# Brain.net
KiCad netlist of a schematic drawn in EAGLE
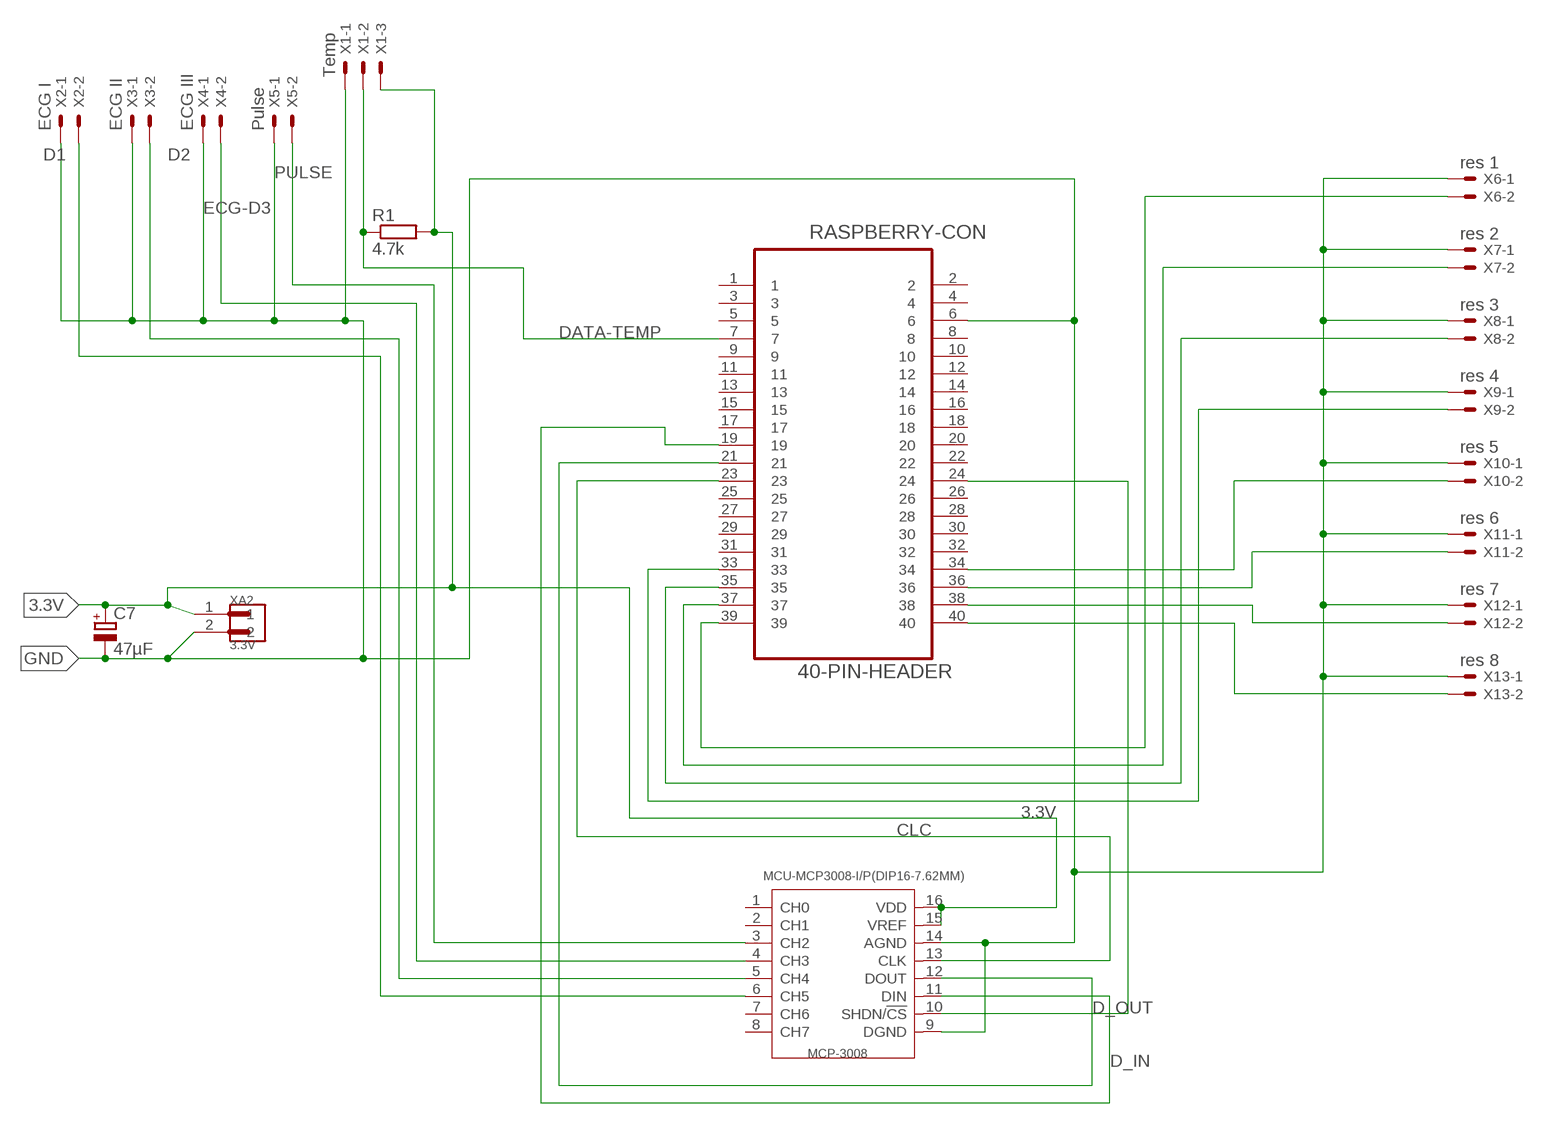
[diagram p0: schematic, sheet 1]

(export (version "E")
  (design (tool "Eeschema 10.0.6"))
  (components
    (comp (ref "C7")
      (value "47µF")
      (footprint "eagle-import:E2,5-6E")
      (libsource (lib "eagle-import") (part "CPOL-EUE2,5-6E"))
    )
    (comp (ref "MCP-3008")
      (value "MCU-MCP3008-I/P(DIP16-7.62MM)")
      (footprint "eagle-import:DIP16-2.54-19.2X7.62MM")
      (fields (field (name "MF") "Microchip") (field (name "MP") "MCP3008-I/P"))
      (libsource (lib "eagle-import") (part "MCU-MCP3008-I/P(DIP16-7.62MM)"))
    )
    (comp (ref "R1")
      (value "4.7k")
      (footprint "eagle-import:0207_7")
      (libsource (lib "eagle-import") (part "R-EU_0207/7"))
    )
    (comp (ref "RASPBERRY-CON")
      (value "40-PIN-HEADER")
      (footprint "eagle-import:SAMTEC_TSW-120-09-F-Q")
      (fields (field (name "MF") "Samtec") (field (name "MP") "TSW-120-09-F-Q"))
      (libsource (lib "eagle-import") (part "TSW-120-09-F-Q"))
    )
    (comp (ref "X1")
      (value "Temp")
      (footprint "eagle-import:JST-XH-03-PACKAGE-LONG-PAD")
      (libsource (lib "eagle-import") (part "JST-XH-03-PIN-LONG-PAD"))
    )
    (comp (ref "X2")
      (value "ECG I")
      (footprint "eagle-import:JST-XH-02-PACKAGE-LONG-PAD")
      (libsource (lib "eagle-import") (part "JST-XH-02-PIN-LONG-PAD"))
    )
    (comp (ref "X3")
      (value "ECG II")
      (footprint "eagle-import:JST-XH-02-PACKAGE-LONG-PAD")
      (libsource (lib "eagle-import") (part "JST-XH-02-PIN-LONG-PAD"))
    )
    (comp (ref "X4")
      (value "ECG III")
      (footprint "eagle-import:JST-XH-02-PACKAGE-LONG-PAD")
      (libsource (lib "eagle-import") (part "JST-XH-02-PIN-LONG-PAD"))
    )
    (comp (ref "X5")
      (value "Pulse")
      (footprint "eagle-import:JST-XH-02-PACKAGE-LONG-PAD")
      (libsource (lib "eagle-import") (part "JST-XH-02-PIN-LONG-PAD"))
    )
    (comp (ref "X6")
      (value "res 1")
      (footprint "eagle-import:JST-XH-02-PACKAGE-LONG-PAD")
      (libsource (lib "eagle-import") (part "JST-XH-02-PIN-LONG-PAD"))
    )
    (comp (ref "X7")
      (value "res 2")
      (footprint "eagle-import:JST-XH-02-PACKAGE-LONG-PAD")
      (libsource (lib "eagle-import") (part "JST-XH-02-PIN-LONG-PAD"))
    )
    (comp (ref "X8")
      (value "res 3")
      (footprint "eagle-import:JST-XH-02-PACKAGE-LONG-PAD")
      (libsource (lib "eagle-import") (part "JST-XH-02-PIN-LONG-PAD"))
    )
    (comp (ref "X9")
      (value "res 4")
      (footprint "eagle-import:JST-XH-02-PACKAGE-LONG-PAD")
      (libsource (lib "eagle-import") (part "JST-XH-02-PIN-LONG-PAD"))
    )
    (comp (ref "X10")
      (value "res 5")
      (footprint "eagle-import:JST-XH-02-PACKAGE-LONG-PAD")
      (libsource (lib "eagle-import") (part "JST-XH-02-PIN-LONG-PAD"))
    )
    (comp (ref "X11")
      (value "res 6")
      (footprint "eagle-import:JST-XH-02-PACKAGE-LONG-PAD")
      (libsource (lib "eagle-import") (part "JST-XH-02-PIN-LONG-PAD"))
    )
    (comp (ref "X12")
      (value "res 7")
      (footprint "eagle-import:JST-XH-02-PACKAGE-LONG-PAD")
      (libsource (lib "eagle-import") (part "JST-XH-02-PIN-LONG-PAD"))
    )
    (comp (ref "X13")
      (value "res 8")
      (footprint "eagle-import:JST-XH-02-PACKAGE-LONG-PAD")
      (libsource (lib "eagle-import") (part "JST-XH-02-PIN-LONG-PAD"))
    )
    (comp (ref "XA2")
      (value "3.3V")
      (footprint "eagle-import:JST_B2P-VH(LF)(SN)")
      (fields (field (name "MF") "JST") (field (name "MP") "B2P-VH_LF__SN_"))
      (libsource (lib "eagle-import") (part "B2P-VH(LF)(SN)"))
    )
  )
  (nets
    (net (code "1") (name "/CLC") (class "Default")
      (node (ref "MCP-3008") (pin "13") (pinfunction "CLK_13") (pintype "output"))
      (node (ref "RASPBERRY-CON") (pin "23") (pinfunction "23_23") (pintype "passive"))
    )
    (net (code "2") (name "/D1") (class "Default")
      (node (ref "MCP-3008") (pin "6") (pinfunction "CH5_6") (pintype "input"))
      (node (ref "X2") (pin "2") (pinfunction "S_2") (pintype "passive"))
    )
    (net (code "3") (name "/D2") (class "Default")
      (node (ref "MCP-3008") (pin "5") (pinfunction "CH4_5") (pintype "input"))
      (node (ref "X3") (pin "2") (pinfunction "S_2") (pintype "passive"))
    )
    (net (code "4") (name "/DATA-TEMP") (class "Default")
      (node (ref "R1") (pin "1") (pinfunction "1_1") (pintype "passive"))
      (node (ref "RASPBERRY-CON") (pin "7") (pinfunction "7_7") (pintype "passive"))
      (node (ref "X1") (pin "2") (pinfunction "S_2") (pintype "passive"))
    )
    (net (code "5") (name "/D_IN") (class "Default")
      (node (ref "MCP-3008") (pin "11") (pinfunction "DIN_11") (pintype "input"))
      (node (ref "RASPBERRY-CON") (pin "19") (pinfunction "19_19") (pintype "passive"))
    )
    (net (code "6") (name "/D_OUT") (class "Default")
      (node (ref "MCP-3008") (pin "12") (pinfunction "DOUT_12") (pintype "input"))
      (node (ref "RASPBERRY-CON") (pin "21") (pinfunction "21_21") (pintype "passive"))
    )
    (net (code "7") (name "/ECG-D3") (class "Default")
      (node (ref "MCP-3008") (pin "4") (pinfunction "CH3_4") (pintype "input"))
      (node (ref "X4") (pin "2") (pinfunction "S_2") (pintype "passive"))
    )
    (net (code "8") (name "/PULSE") (class "Default")
      (node (ref "MCP-3008") (pin "3") (pinfunction "CH2_3") (pintype "output"))
      (node (ref "X5") (pin "2") (pinfunction "S_2") (pintype "passive"))
    )
    (net (code "9") (name "3.3V") (class "Default")
      (node (ref "C7") (pin "+") (pinfunction "+_+") (pintype "passive"))
      (node (ref "MCP-3008") (pin "15") (pinfunction "VREF_15") (pintype "input"))
      (node (ref "MCP-3008") (pin "16") (pinfunction "VDD_16") (pintype "power_in"))
      (node (ref "R1") (pin "2") (pinfunction "2_2") (pintype "passive"))
      (node (ref "X1") (pin "3") (pinfunction "S_3") (pintype "passive"))
      (node (ref "XA2") (pin "1") (pinfunction "1_1") (pintype "passive"))
    )
    (net (code "10") (name "GND") (class "Default")
      (node (ref "C7") (pin "-") (pinfunction "-_-") (pintype "passive"))
      (node (ref "MCP-3008") (pin "14") (pinfunction "AGND_14") (pintype "input"))
      (node (ref "MCP-3008") (pin "9") (pinfunction "DGND_9") (pintype "output"))
      (node (ref "RASPBERRY-CON") (pin "6") (pinfunction "6_6") (pintype "passive"))
      (node (ref "X1") (pin "1") (pinfunction "S_1") (pintype "passive"))
      (node (ref "X10") (pin "1") (pinfunction "S_1") (pintype "passive"))
      (node (ref "X11") (pin "1") (pinfunction "S_1") (pintype "passive"))
      (node (ref "X12") (pin "1") (pinfunction "S_1") (pintype "passive"))
      (node (ref "X13") (pin "1") (pinfunction "S_1") (pintype "passive"))
      (node (ref "X2") (pin "1") (pinfunction "S_1") (pintype "passive"))
      (node (ref "X3") (pin "1") (pinfunction "S_1") (pintype "passive"))
      (node (ref "X4") (pin "1") (pinfunction "S_1") (pintype "passive"))
      (node (ref "X5") (pin "1") (pinfunction "S_1") (pintype "passive"))
      (node (ref "X6") (pin "1") (pinfunction "S_1") (pintype "passive"))
      (node (ref "X7") (pin "1") (pinfunction "S_1") (pintype "passive"))
      (node (ref "X8") (pin "1") (pinfunction "S_1") (pintype "passive"))
      (node (ref "X9") (pin "1") (pinfunction "S_1") (pintype "passive"))
      (node (ref "XA2") (pin "2") (pinfunction "2_2") (pintype "passive"))
    )
    (net (code "11") (name "Net-(MCP-3008-SHDN{slash}~{CS})") (class "Default")
      (node (ref "MCP-3008") (pin "10") (pinfunction "SHDN/~{CS}_10") (pintype "output"))
      (node (ref "RASPBERRY-CON") (pin "24") (pinfunction "24_24") (pintype "passive"))
    )
    (net (code "12") (name "Net-(X6B-S)") (class "Default")
      (node (ref "RASPBERRY-CON") (pin "39") (pinfunction "39_39") (pintype "passive"))
      (node (ref "X6") (pin "2") (pinfunction "S_2") (pintype "passive"))
    )
    (net (code "13") (name "Net-(X7B-S)") (class "Default")
      (node (ref "RASPBERRY-CON") (pin "37") (pinfunction "37_37") (pintype "passive"))
      (node (ref "X7") (pin "2") (pinfunction "S_2") (pintype "passive"))
    )
    (net (code "14") (name "Net-(X8B-S)") (class "Default")
      (node (ref "RASPBERRY-CON") (pin "35") (pinfunction "35_35") (pintype "passive"))
      (node (ref "X8") (pin "2") (pinfunction "S_2") (pintype "passive"))
    )
    (net (code "15") (name "Net-(X9B-S)") (class "Default")
      (node (ref "RASPBERRY-CON") (pin "33") (pinfunction "33_33") (pintype "passive"))
      (node (ref "X9") (pin "2") (pinfunction "S_2") (pintype "passive"))
    )
    (net (code "16") (name "Net-(X10B-S)") (class "Default")
      (node (ref "RASPBERRY-CON") (pin "34") (pinfunction "34_34") (pintype "passive"))
      (node (ref "X10") (pin "2") (pinfunction "S_2") (pintype "passive"))
    )
    (net (code "17") (name "Net-(X11B-S)") (class "Default")
      (node (ref "RASPBERRY-CON") (pin "36") (pinfunction "36_36") (pintype "passive"))
      (node (ref "X11") (pin "2") (pinfunction "S_2") (pintype "passive"))
    )
    (net (code "18") (name "Net-(X12B-S)") (class "Default")
      (node (ref "RASPBERRY-CON") (pin "38") (pinfunction "38_38") (pintype "passive"))
      (node (ref "X12") (pin "2") (pinfunction "S_2") (pintype "passive"))
    )
    (net (code "19") (name "Net-(X13B-S)") (class "Default")
      (node (ref "RASPBERRY-CON") (pin "40") (pinfunction "40_40") (pintype "passive"))
      (node (ref "X13") (pin "2") (pinfunction "S_2") (pintype "passive"))
    )
    (net (code "20") (name "unconnected-(MCP-3008-CH0-Pad1)") (class "Default")
      (node (ref "MCP-3008") (pin "1") (pinfunction "CH0_1") (pintype "output"))
    )
    (net (code "21") (name "unconnected-(MCP-3008-CH1-Pad2)") (class "Default")
      (node (ref "MCP-3008") (pin "2") (pinfunction "CH1_2") (pintype "input"))
    )
    (net (code "22") (name "unconnected-(MCP-3008-CH6-Pad7)") (class "Default")
      (node (ref "MCP-3008") (pin "7") (pinfunction "CH6_7") (pintype "output"))
    )
    (net (code "23") (name "unconnected-(MCP-3008-CH7-Pad8)") (class "Default")
      (node (ref "MCP-3008") (pin "8") (pinfunction "CH7_8") (pintype "input"))
    )
    (net (code "24") (name "unconnected-(RASPBERRY-CON-Pad1)") (class "Default")
      (node (ref "RASPBERRY-CON") (pin "1") (pinfunction "1_1") (pintype "passive"))
    )
    (net (code "25") (name "unconnected-(RASPBERRY-CON-Pad2)") (class "Default")
      (node (ref "RASPBERRY-CON") (pin "2") (pinfunction "2_2") (pintype "passive"))
    )
    (net (code "26") (name "unconnected-(RASPBERRY-CON-Pad3)") (class "Default")
      (node (ref "RASPBERRY-CON") (pin "3") (pinfunction "3_3") (pintype "passive"))
    )
    (net (code "27") (name "unconnected-(RASPBERRY-CON-Pad4)") (class "Default")
      (node (ref "RASPBERRY-CON") (pin "4") (pinfunction "4_4") (pintype "passive"))
    )
    (net (code "28") (name "unconnected-(RASPBERRY-CON-Pad5)") (class "Default")
      (node (ref "RASPBERRY-CON") (pin "5") (pinfunction "5_5") (pintype "passive"))
    )
    (net (code "29") (name "unconnected-(RASPBERRY-CON-Pad8)") (class "Default")
      (node (ref "RASPBERRY-CON") (pin "8") (pinfunction "8_8") (pintype "passive"))
    )
    (net (code "30") (name "unconnected-(RASPBERRY-CON-Pad9)") (class "Default")
      (node (ref "RASPBERRY-CON") (pin "9") (pinfunction "9_9") (pintype "passive"))
    )
    (net (code "31") (name "unconnected-(RASPBERRY-CON-Pad10)") (class "Default")
      (node (ref "RASPBERRY-CON") (pin "10") (pinfunction "10_10") (pintype "passive"))
    )
    (net (code "32") (name "unconnected-(RASPBERRY-CON-Pad11)") (class "Default")
      (node (ref "RASPBERRY-CON") (pin "11") (pinfunction "11_11") (pintype "passive"))
    )
    (net (code "33") (name "unconnected-(RASPBERRY-CON-Pad12)") (class "Default")
      (node (ref "RASPBERRY-CON") (pin "12") (pinfunction "12_12") (pintype "passive"))
    )
    (net (code "34") (name "unconnected-(RASPBERRY-CON-Pad13)") (class "Default")
      (node (ref "RASPBERRY-CON") (pin "13") (pinfunction "13_13") (pintype "passive"))
    )
    (net (code "35") (name "unconnected-(RASPBERRY-CON-Pad14)") (class "Default")
      (node (ref "RASPBERRY-CON") (pin "14") (pinfunction "14_14") (pintype "passive"))
    )
    (net (code "36") (name "unconnected-(RASPBERRY-CON-Pad15)") (class "Default")
      (node (ref "RASPBERRY-CON") (pin "15") (pinfunction "15_15") (pintype "passive"))
    )
    (net (code "37") (name "unconnected-(RASPBERRY-CON-Pad16)") (class "Default")
      (node (ref "RASPBERRY-CON") (pin "16") (pinfunction "16_16") (pintype "passive"))
    )
    (net (code "38") (name "unconnected-(RASPBERRY-CON-Pad17)") (class "Default")
      (node (ref "RASPBERRY-CON") (pin "17") (pinfunction "17_17") (pintype "passive"))
    )
    (net (code "39") (name "unconnected-(RASPBERRY-CON-Pad18)") (class "Default")
      (node (ref "RASPBERRY-CON") (pin "18") (pinfunction "18_18") (pintype "passive"))
    )
    (net (code "40") (name "unconnected-(RASPBERRY-CON-Pad20)") (class "Default")
      (node (ref "RASPBERRY-CON") (pin "20") (pinfunction "20_20") (pintype "passive"))
    )
    (net (code "41") (name "unconnected-(RASPBERRY-CON-Pad22)") (class "Default")
      (node (ref "RASPBERRY-CON") (pin "22") (pinfunction "22_22") (pintype "passive"))
    )
    (net (code "42") (name "unconnected-(RASPBERRY-CON-Pad25)") (class "Default")
      (node (ref "RASPBERRY-CON") (pin "25") (pinfunction "25_25") (pintype "passive"))
    )
    (net (code "43") (name "unconnected-(RASPBERRY-CON-Pad26)") (class "Default")
      (node (ref "RASPBERRY-CON") (pin "26") (pinfunction "26_26") (pintype "passive"))
    )
    (net (code "44") (name "unconnected-(RASPBERRY-CON-Pad27)") (class "Default")
      (node (ref "RASPBERRY-CON") (pin "27") (pinfunction "27_27") (pintype "passive"))
    )
    (net (code "45") (name "unconnected-(RASPBERRY-CON-Pad28)") (class "Default")
      (node (ref "RASPBERRY-CON") (pin "28") (pinfunction "28_28") (pintype "passive"))
    )
    (net (code "46") (name "unconnected-(RASPBERRY-CON-Pad29)") (class "Default")
      (node (ref "RASPBERRY-CON") (pin "29") (pinfunction "29_29") (pintype "passive"))
    )
    (net (code "47") (name "unconnected-(RASPBERRY-CON-Pad30)") (class "Default")
      (node (ref "RASPBERRY-CON") (pin "30") (pinfunction "30_30") (pintype "passive"))
    )
    (net (code "48") (name "unconnected-(RASPBERRY-CON-Pad31)") (class "Default")
      (node (ref "RASPBERRY-CON") (pin "31") (pinfunction "31_31") (pintype "passive"))
    )
    (net (code "49") (name "unconnected-(RASPBERRY-CON-Pad32)") (class "Default")
      (node (ref "RASPBERRY-CON") (pin "32") (pinfunction "32_32") (pintype "passive"))
    )
  )
)
